# Sheet1.net
KiCad netlist of a schematic drawn in Altium Designer
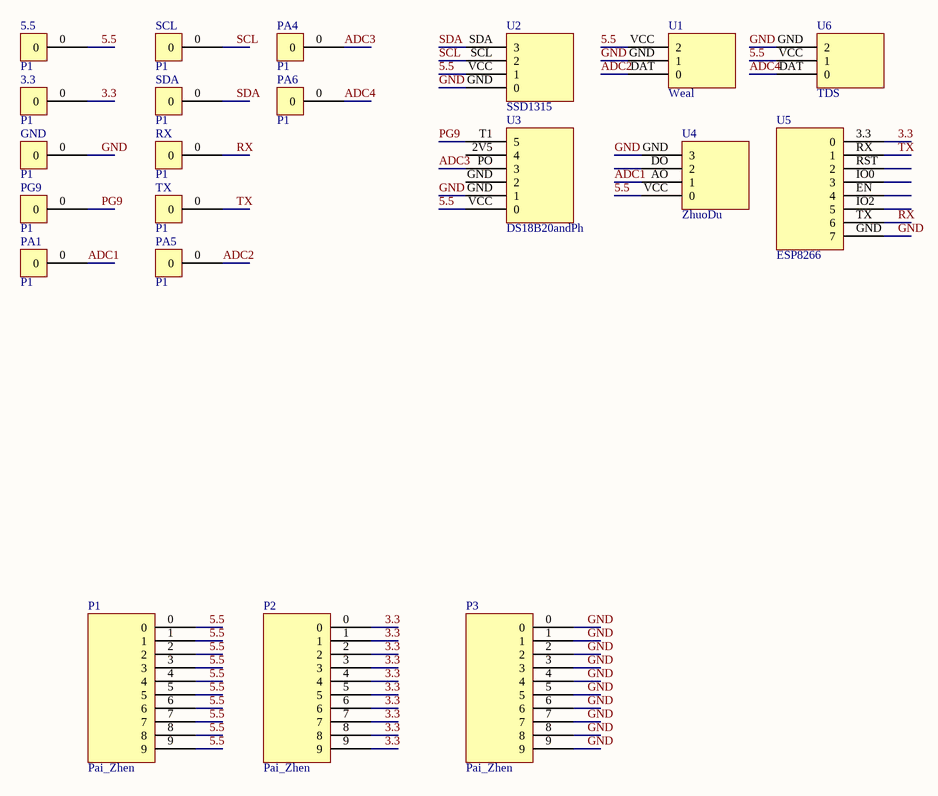
[diagram p0: Sheet1.SchDoc]

(export (version "E")
  (design (tool "Eeschema 10.0.6"))
  (components
    (comp (ref "3.3") (value "P1") (footprint "PAI_1") (libsource (lib "Schlib1") (part "P1")))
    (comp (ref "5.5") (value "P1") (footprint "PAI_1") (libsource (lib "Schlib1") (part "P1")))
    (comp (ref "GND") (value "P1") (footprint "PAI_1") (libsource (lib "Schlib1") (part "P1")))
    (comp (ref "P1") (value "Pai_Zhen") (footprint "PAI_ZHEN") (libsource (lib "Schlib1") (part "Pai_Zhen")))
    (comp (ref "P2") (value "Pai_Zhen") (footprint "PAI_ZHEN") (libsource (lib "Schlib1") (part "Pai_Zhen")))
    (comp (ref "P3") (value "Pai_Zhen") (footprint "PAI_ZHEN") (libsource (lib "Schlib1") (part "Pai_Zhen")))
    (comp (ref "PA1") (value "P1") (footprint "PAI_1") (libsource (lib "Schlib1") (part "P1")))
    (comp (ref "PA4") (value "P1") (footprint "PAI_1") (libsource (lib "Schlib1") (part "P1")))
    (comp (ref "PA5") (value "P1") (footprint "PAI_1") (libsource (lib "Schlib1") (part "P1")))
    (comp (ref "PA6") (value "P1") (footprint "PAI_1") (libsource (lib "Schlib1") (part "P1")))
    (comp (ref "PG9") (value "P1") (footprint "PAI_1") (libsource (lib "Schlib1") (part "P1")))
    (comp (ref "RX") (value "P1") (footprint "PAI_1") (libsource (lib "Schlib1") (part "P1")))
    (comp (ref "SCL") (value "P1") (footprint "PAI_1") (libsource (lib "Schlib1") (part "P1")))
    (comp (ref "SDA") (value "P1") (footprint "PAI_1") (libsource (lib "Schlib1") (part "P1")))
    (comp (ref "TX") (value "P1") (footprint "PAI_1") (libsource (lib "Schlib1") (part "P1")))
    (comp (ref "U1") (value "Weal") (footprint "Weal") (libsource (lib "Schlib1") (part "Weal")))
    (comp (ref "U2") (value "SSD1315") (footprint "ssd1315") (libsource (lib "Schlib1") (part "SSD1315")))
    (comp (ref "U3")
      (value "DS18B20andPh")
      (footprint "DS18B20")
      (libsource (lib "Schlib1") (part "DS18B20andPh"))
    )
    (comp (ref "U4") (value "ZhuoDu") (footprint "ZhuoDu") (libsource (lib "Schlib1") (part "ZhuoDu")))
    (comp (ref "U5") (value "ESP8266") (footprint "ESP8266") (libsource (lib "Schlib1") (part "ESP8266")))
    (comp (ref "U6") (value "TDS") (footprint "TDS") (libsource (lib "Schlib1") (part "TDS")))
  )
  (nets
    (net (code "1") (name "/3.3") (class "Default")
      (node (ref "3.3") (pin "0") (pinfunction "0_0") (pintype "passive"))
      (node (ref "P2") (pin "0") (pinfunction "0_0") (pintype "passive"))
      (node (ref "P2") (pin "1") (pinfunction "1_1") (pintype "passive"))
      (node (ref "P2") (pin "2") (pinfunction "2_2") (pintype "passive"))
      (node (ref "P2") (pin "3") (pinfunction "3_3") (pintype "passive"))
      (node (ref "P2") (pin "4") (pinfunction "4_4") (pintype "passive"))
      (node (ref "P2") (pin "5") (pinfunction "5_5") (pintype "passive"))
      (node (ref "P2") (pin "6") (pinfunction "6_6") (pintype "passive"))
      (node (ref "P2") (pin "7") (pinfunction "7_7") (pintype "passive"))
      (node (ref "P2") (pin "8") (pinfunction "8_8") (pintype "passive"))
      (node (ref "P2") (pin "9") (pinfunction "9_9") (pintype "passive"))
      (node (ref "U5") (pin "3.3") (pinfunction "0_3.3") (pintype "passive"))
    )
    (net (code "2") (name "/5.5") (class "Default")
      (node (ref "5.5") (pin "0") (pinfunction "0_0") (pintype "passive"))
      (node (ref "P1") (pin "0") (pinfunction "0_0") (pintype "passive"))
      (node (ref "P1") (pin "1") (pinfunction "1_1") (pintype "passive"))
      (node (ref "P1") (pin "2") (pinfunction "2_2") (pintype "passive"))
      (node (ref "P1") (pin "3") (pinfunction "3_3") (pintype "passive"))
      (node (ref "P1") (pin "4") (pinfunction "4_4") (pintype "passive"))
      (node (ref "P1") (pin "5") (pinfunction "5_5") (pintype "passive"))
      (node (ref "P1") (pin "6") (pinfunction "6_6") (pintype "passive"))
      (node (ref "P1") (pin "7") (pinfunction "7_7") (pintype "passive"))
      (node (ref "P1") (pin "8") (pinfunction "8_8") (pintype "passive"))
      (node (ref "P1") (pin "9") (pinfunction "9_9") (pintype "passive"))
      (node (ref "U1") (pin "VCC") (pinfunction "2_VCC") (pintype "passive"))
      (node (ref "U2") (pin "VCC") (pinfunction "1_VCC") (pintype "passive"))
      (node (ref "U3") (pin "VCC") (pinfunction "0_VCC") (pintype "passive"))
      (node (ref "U4") (pin "VCC") (pinfunction "0_VCC") (pintype "passive"))
      (node (ref "U6") (pin "VCC") (pinfunction "1_VCC") (pintype "passive"))
    )
    (net (code "3") (name "/ADC1") (class "Default")
      (node (ref "PA1") (pin "0") (pinfunction "0_0") (pintype "passive"))
      (node (ref "U4") (pin "AO") (pinfunction "1_AO") (pintype "passive"))
    )
    (net (code "4") (name "/ADC2") (class "Default")
      (node (ref "PA5") (pin "0") (pinfunction "0_0") (pintype "passive"))
      (node (ref "U1") (pin "DAT") (pinfunction "0_DAT") (pintype "passive"))
    )
    (net (code "5") (name "/ADC3") (class "Default")
      (node (ref "PA4") (pin "0") (pinfunction "0_0") (pintype "passive"))
      (node (ref "U3") (pin "PO") (pinfunction "3_PO") (pintype "passive"))
    )
    (net (code "6") (name "/ADC4") (class "Default")
      (node (ref "PA6") (pin "0") (pinfunction "0_0") (pintype "passive"))
      (node (ref "U6") (pin "DAT") (pinfunction "0_DAT") (pintype "passive"))
    )
    (net (code "7") (name "/GND") (class "Default")
      (node (ref "GND") (pin "0") (pinfunction "0_0") (pintype "passive"))
      (node (ref "P3") (pin "0") (pinfunction "0_0") (pintype "passive"))
      (node (ref "P3") (pin "1") (pinfunction "1_1") (pintype "passive"))
      (node (ref "P3") (pin "2") (pinfunction "2_2") (pintype "passive"))
      (node (ref "P3") (pin "3") (pinfunction "3_3") (pintype "passive"))
      (node (ref "P3") (pin "4") (pinfunction "4_4") (pintype "passive"))
      (node (ref "P3") (pin "5") (pinfunction "5_5") (pintype "passive"))
      (node (ref "P3") (pin "6") (pinfunction "6_6") (pintype "passive"))
      (node (ref "P3") (pin "7") (pinfunction "7_7") (pintype "passive"))
      (node (ref "P3") (pin "8") (pinfunction "8_8") (pintype "passive"))
      (node (ref "P3") (pin "9") (pinfunction "9_9") (pintype "passive"))
      (node (ref "U1") (pin "GND") (pinfunction "1_GND") (pintype "passive"))
      (node (ref "U2") (pin "GND") (pinfunction "0_GND") (pintype "passive"))
      (node (ref "U3") (pin "GND") (pinfunction "1_GND") (pintype "passive"))
      (node (ref "U4") (pin "GND") (pinfunction "3_GND") (pintype "passive"))
      (node (ref "U5") (pin "GND") (pinfunction "7_GND") (pintype "passive"))
      (node (ref "U6") (pin "GND") (pinfunction "2_GND") (pintype "passive"))
    )
    (net (code "8") (name "/PG9") (class "Default")
      (node (ref "PG9") (pin "0") (pinfunction "0_0") (pintype "passive"))
      (node (ref "U3") (pin "T1") (pinfunction "5_T1") (pintype "passive"))
    )
    (net (code "9") (name "/RX") (class "Default")
      (node (ref "RX") (pin "0") (pinfunction "0_0") (pintype "passive"))
      (node (ref "U5") (pin "TX") (pinfunction "6_TX") (pintype "passive"))
    )
    (net (code "10") (name "/SCL") (class "Default")
      (node (ref "SCL") (pin "0") (pinfunction "0_0") (pintype "passive"))
      (node (ref "U2") (pin "SCL") (pinfunction "2_SCL") (pintype "passive"))
    )
    (net (code "11") (name "/SDA") (class "Default")
      (node (ref "SDA") (pin "0") (pinfunction "0_0") (pintype "passive"))
      (node (ref "U2") (pin "SDA") (pinfunction "3_SDA") (pintype "passive"))
    )
    (net (code "12") (name "/TX") (class "Default")
      (node (ref "TX") (pin "0") (pinfunction "0_0") (pintype "passive"))
      (node (ref "U5") (pin "RX") (pinfunction "1_RX") (pintype "passive"))
    )
    (net (code "13") (name "unconnected-(U3-2-PadGND)") (class "Default")
      (node (ref "U3") (pin "GND") (pinfunction "2_GND") (pintype "passive"))
    )
    (net (code "14") (name "unconnected-(U3-4-Pad2V5)") (class "Default")
      (node (ref "U3") (pin "2V5") (pinfunction "4_2V5") (pintype "passive"))
    )
    (net (code "15") (name "unconnected-(U4-2-PadDO)") (class "Default")
      (node (ref "U4") (pin "DO") (pinfunction "2_DO") (pintype "passive"))
    )
    (net (code "16") (name "unconnected-(U5-2-PadRST)") (class "Default")
      (node (ref "U5") (pin "RST") (pinfunction "2_RST") (pintype "passive"))
    )
    (net (code "17") (name "unconnected-(U5-3-PadIO0)") (class "Default")
      (node (ref "U5") (pin "IO0") (pinfunction "3_IO0") (pintype "passive"))
    )
    (net (code "18") (name "unconnected-(U5-4-PadEN)") (class "Default")
      (node (ref "U5") (pin "EN") (pinfunction "4_EN") (pintype "passive"))
    )
    (net (code "19") (name "unconnected-(U5-5-PadIO2)") (class "Default")
      (node (ref "U5") (pin "IO2") (pinfunction "5_IO2") (pintype "passive"))
    )
  )
)
